# mini-v1_12-macrofab.net
KiCad netlist of a schematic drawn in EAGLE
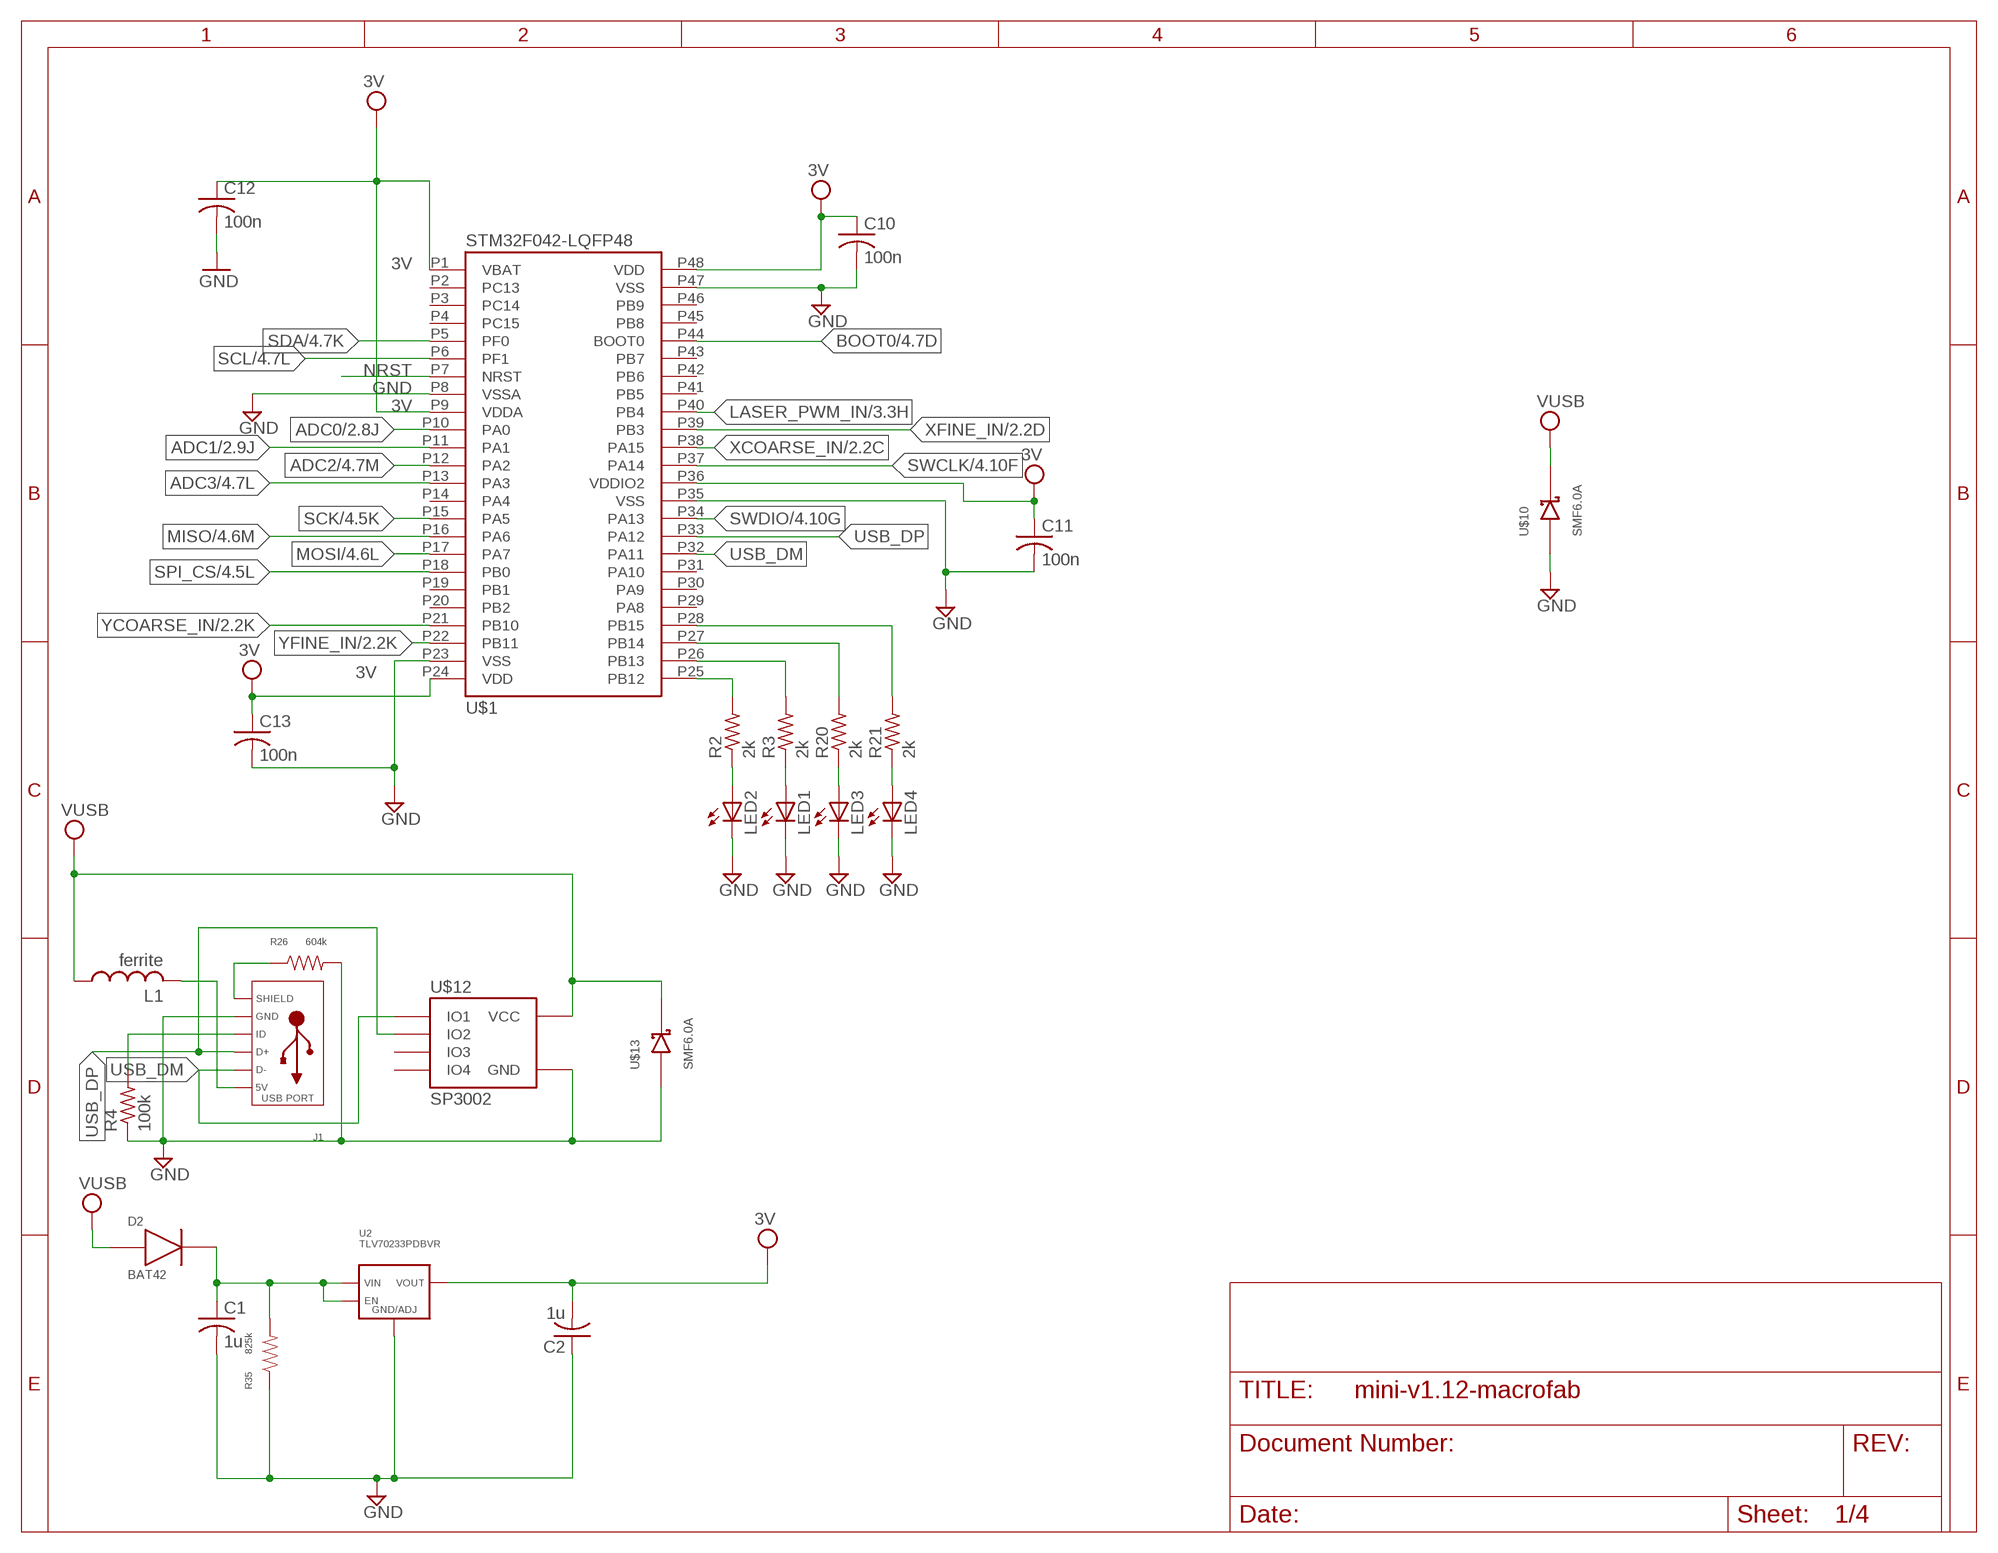
[diagram p0: schematic, sheet 1]
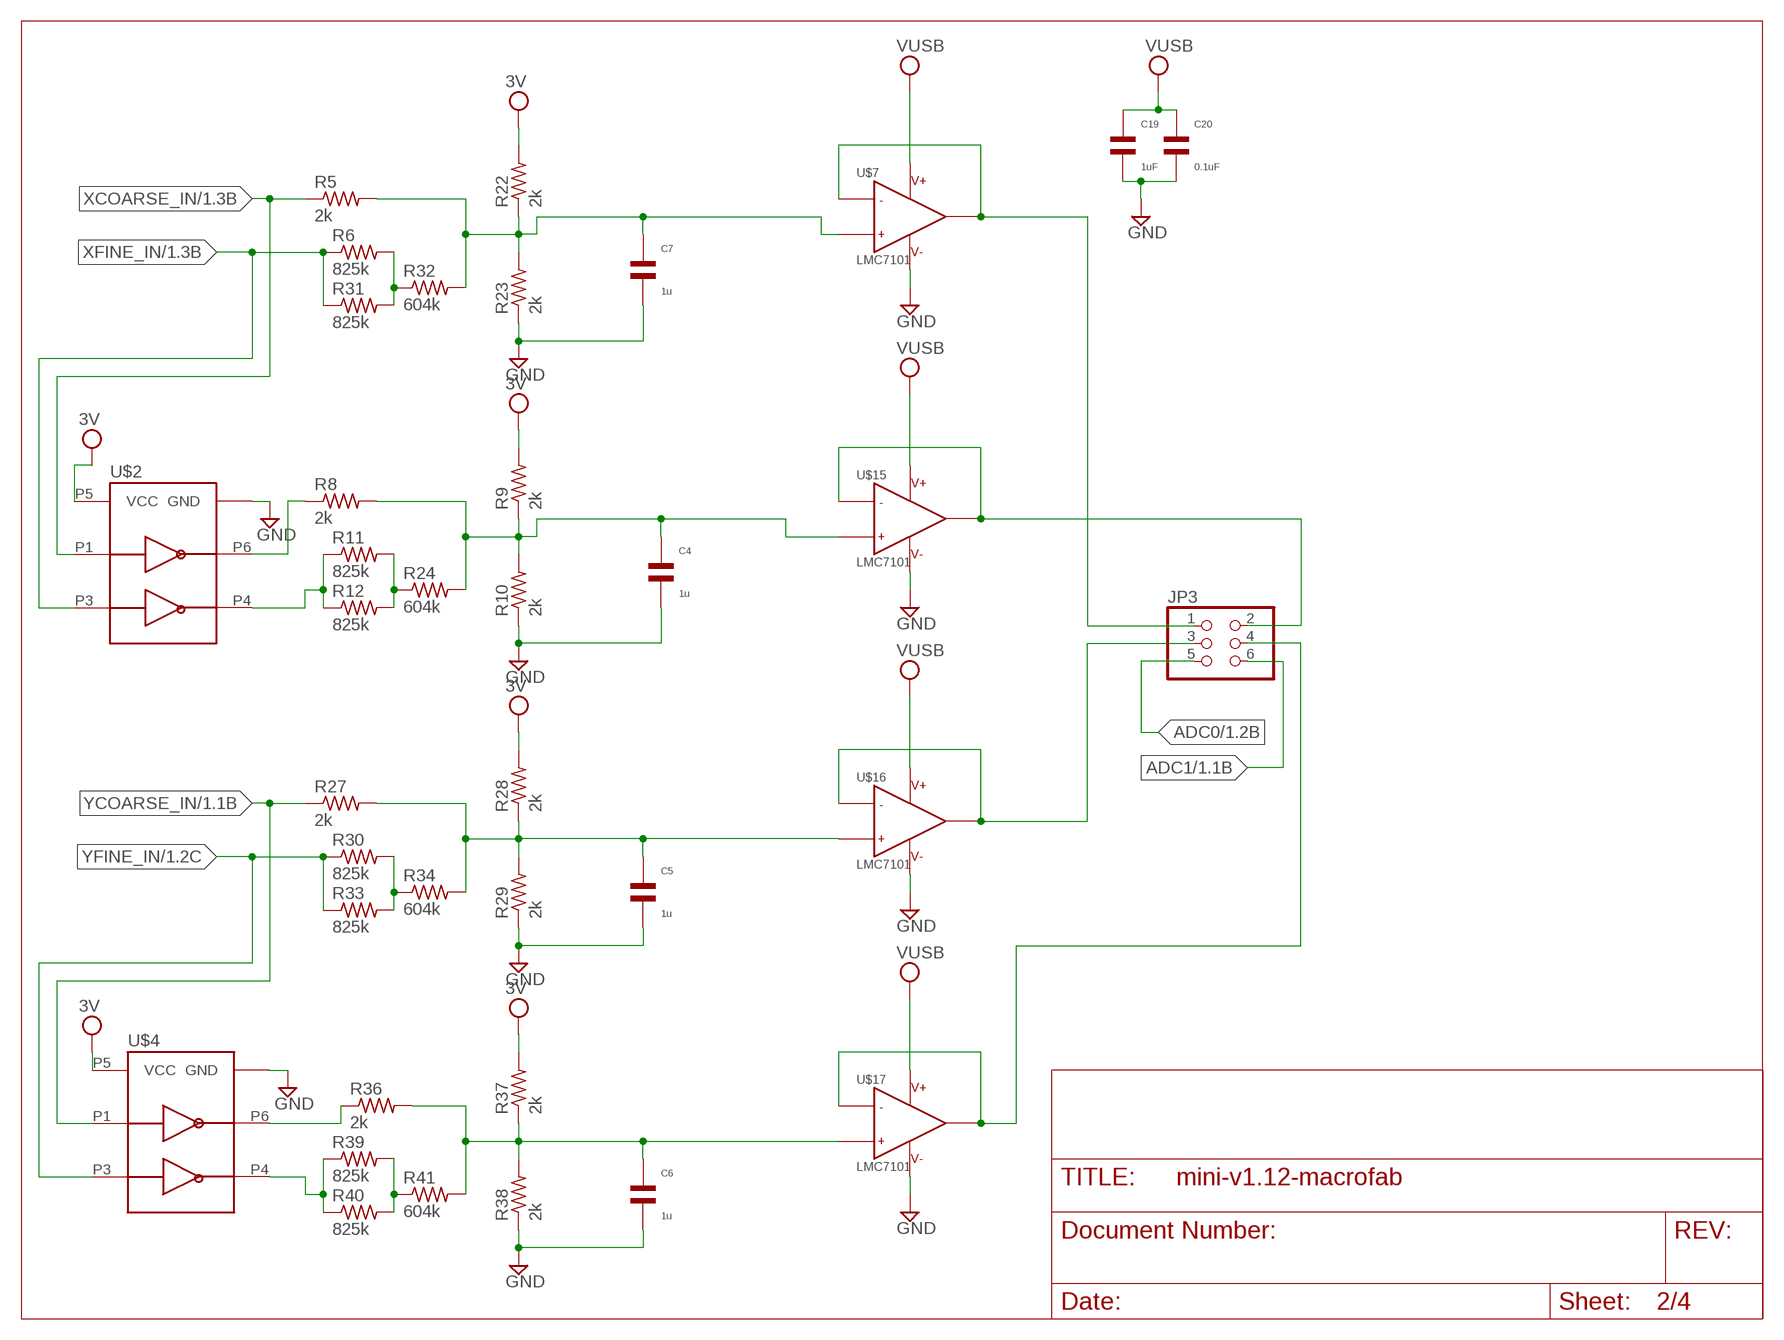
[diagram p1: schematic, sheet 2]
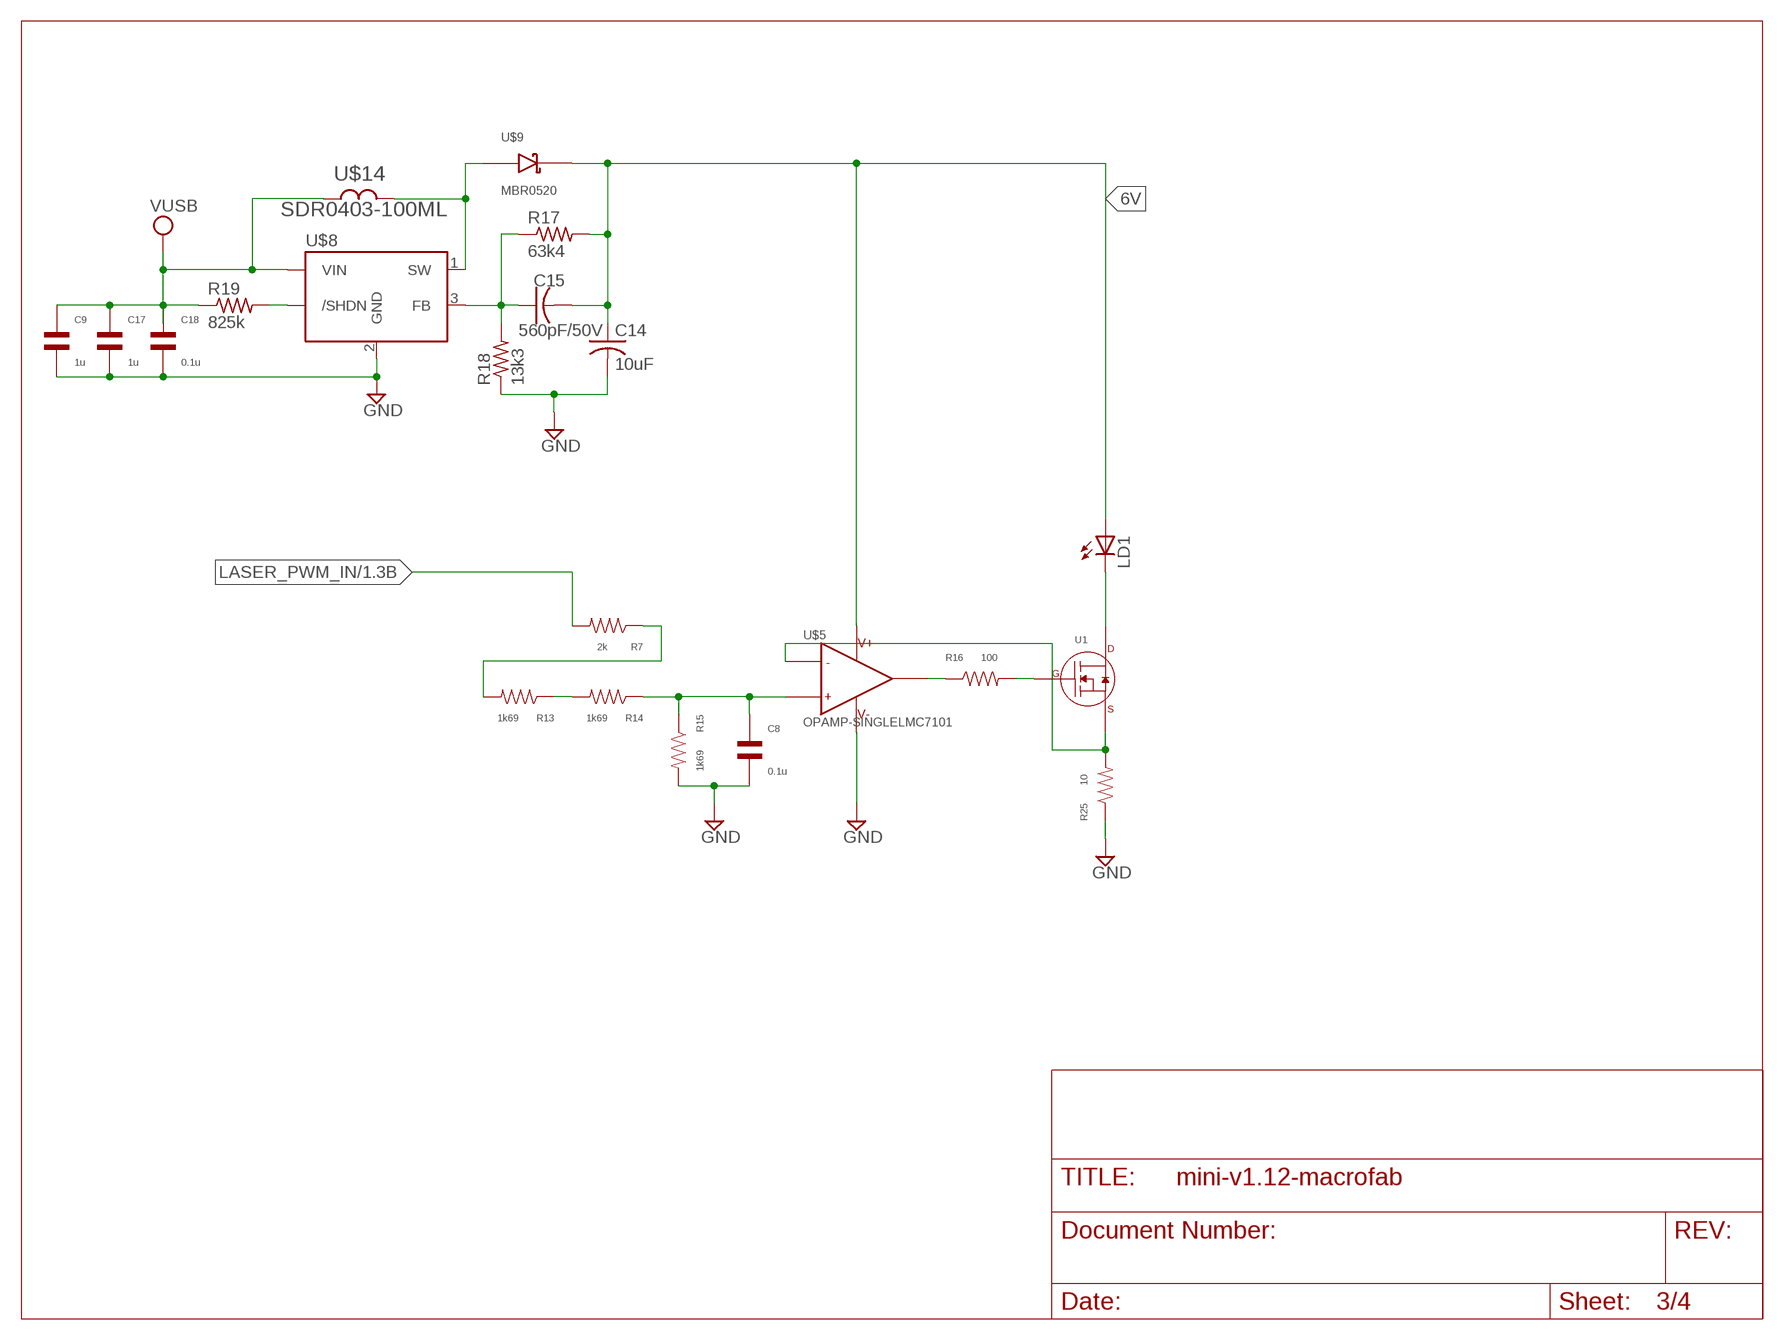
[diagram p2: schematic, sheet 3]
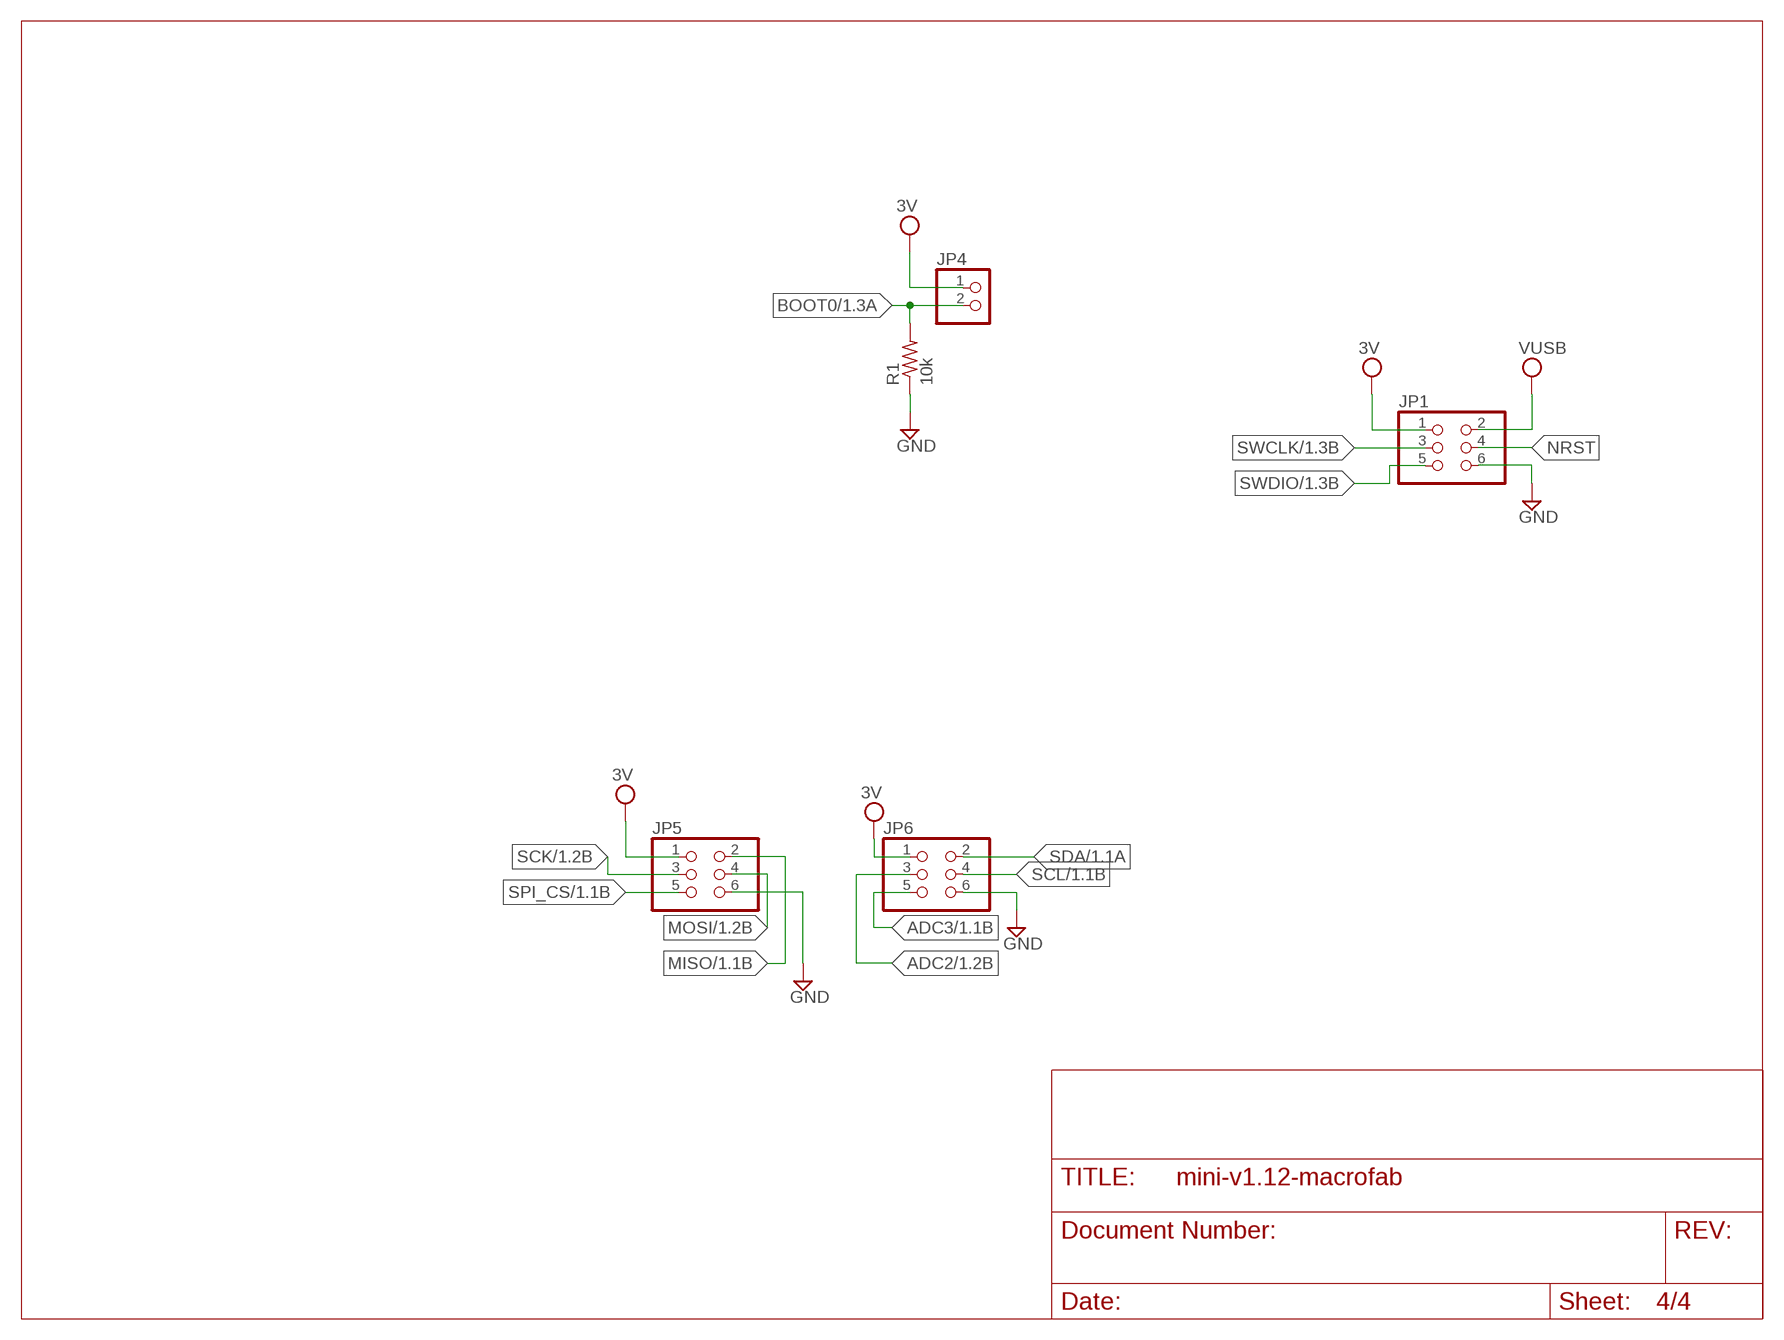
[diagram p3: schematic, sheet 4]

(export (version "E")
  (design (tool "Eeschema 10.0.6"))
  (components
    (comp (ref "C8")
      (value "0.1u")
      (footprint "eagle-import:C0603")
      (libsource (lib "eagle-import") (part "CAPACITOR_NP_0603"))
    )
    (comp (ref "C9")
      (value "1u")
      (footprint "eagle-import:C0603")
      (libsource (lib "eagle-import") (part "CAPACITOR_NP_0603"))
    )
    (comp (ref "C14")
      (value "10uF")
      (footprint "eagle-import:C0603")
      (libsource (lib "eagle-import") (part "C-USC0603"))
    )
    (comp (ref "C15")
      (value "560pF/50V")
      (footprint "eagle-import:C0603")
      (libsource (lib "eagle-import") (part "C-USC0603"))
    )
    (comp (ref "C17")
      (value "1u")
      (footprint "eagle-import:C0603")
      (libsource (lib "eagle-import") (part "CAPACITOR_NP_0603"))
    )
    (comp (ref "C18")
      (value "0.1u")
      (footprint "eagle-import:C0603")
      (libsource (lib "eagle-import") (part "CAPACITOR_NP_0603"))
    )
    (comp (ref "LD1")
      (value "LASERDIODELD2")
      (footprint "eagle-import:LASERDIODE2")
      (fields (field (name "MPN") "3 x (0552-2-15-15-11-27-10-0)"))
      (libsource (lib "eagle-import") (part "LASERDIODELD2"))
    )
    (comp (ref "R7")
      (value "2k")
      (footprint "eagle-import:R0603")
      (libsource (lib "eagle-import") (part "RESISTOR_0603"))
    )
    (comp (ref "R13")
      (value "1k69")
      (footprint "eagle-import:R0603")
      (libsource (lib "eagle-import") (part "RESISTOR_0603"))
    )
    (comp (ref "R14")
      (value "1k69")
      (footprint "eagle-import:R0603")
      (libsource (lib "eagle-import") (part "RESISTOR_0603"))
    )
    (comp (ref "R15")
      (value "1k69")
      (footprint "eagle-import:R0603")
      (libsource (lib "eagle-import") (part "RESISTOR_0603"))
    )
    (comp (ref "R16")
      (value "100")
      (footprint "eagle-import:R0603")
      (libsource (lib "eagle-import") (part "RESISTOR_0603"))
    )
    (comp (ref "R17")
      (value "63k4")
      (footprint "eagle-import:R0603")
      (libsource (lib "eagle-import") (part "R-US_R0603"))
    )
    (comp (ref "R18")
      (value "13k3")
      (footprint "eagle-import:R0603")
      (libsource (lib "eagle-import") (part "R-US_R0603"))
    )
    (comp (ref "R19")
      (value "825k")
      (footprint "eagle-import:R0603")
      (libsource (lib "eagle-import") (part "R-US_R0603"))
    )
    (comp (ref "R25")
      (value "10")
      (footprint "eagle-import:R0603")
      (libsource (lib "eagle-import") (part "RESISTOR_0603"))
    )
    (comp (ref "U$5")
      (value "OPAMP-SINGLELMC7101")
      (footprint "eagle-import:SOT23-5")
      (libsource (lib "eagle-import") (part "OPAMP-SINGLELMC7101"))
    )
    (comp (ref "U$8")
      (value "LMR62014")
      (footprint "eagle-import:SOT23-5")
      (libsource (lib "eagle-import") (part "LMR62014"))
    )
    (comp (ref "U$9")
      (value "MBR0520")
      (footprint "eagle-import:SOD123")
      (libsource (lib "eagle-import") (part "MBR0520"))
    )
    (comp (ref "U$14")
      (value "SDR0403-100ML")
      (footprint "eagle-import:SDR0403")
      (libsource (lib "eagle-import") (part "SDR0403"))
    )
    (comp (ref "U1")
      (value "N-CHANNEL_FET_SOT-23-3")
      (footprint "eagle-import:SOT-23-3")
      (libsource (lib "eagle-import") (part "N-CHANNEL_FET_SOT-23-3"))
    )
    (comp (ref "C1")
      (value "1u")
      (footprint "eagle-import:C0603")
      (libsource (lib "eagle-import") (part "C-USC0603"))
    )
    (comp (ref "C2")
      (value "1u")
      (footprint "eagle-import:C0603")
      (libsource (lib "eagle-import") (part "C-USC0603"))
    )
    (comp (ref "C10")
      (value "100n")
      (footprint "eagle-import:C0603")
      (libsource (lib "eagle-import") (part "C-USC0603"))
    )
    (comp (ref "C11")
      (value "100n")
      (footprint "eagle-import:C0603")
      (libsource (lib "eagle-import") (part "C-USC0603"))
    )
    (comp (ref "C12")
      (value "100n")
      (footprint "eagle-import:C0603")
      (libsource (lib "eagle-import") (part "C-USC0603"))
    )
    (comp (ref "C13")
      (value "100n")
      (footprint "eagle-import:C0603")
      (libsource (lib "eagle-import") (part "C-USC0603"))
    )
    (comp (ref "D2")
      (value "BAT42")
      (footprint "eagle-import:SOD323")
      (libsource (lib "eagle-import") (part "BAT60A"))
    )
    (comp (ref "J1")
      (value "USB_MICRO_RIGHT")
      (footprint "eagle-import:MICROUSB-RIGHT")
      (libsource (lib "eagle-import") (part "USB_MICRO_RIGHT"))
    )
    (comp (ref "L1")
      (value "ferrite")
      (footprint "eagle-import:C0603")
      (libsource (lib "eagle-import") (part "L-US"))
    )
    (comp (ref "LED1")
      (value "LEDCHIP-LED0603")
      (footprint "eagle-import:CHIP-LED0603")
      (libsource (lib "eagle-import") (part "LEDCHIP-LED0603"))
    )
    (comp (ref "LED2")
      (value "LEDCHIP-LED0603")
      (footprint "eagle-import:CHIP-LED0603")
      (libsource (lib "eagle-import") (part "LEDCHIP-LED0603"))
    )
    (comp (ref "LED3")
      (value "LEDCHIP-LED0603")
      (footprint "eagle-import:CHIP-LED0603")
      (libsource (lib "eagle-import") (part "LEDCHIP-LED0603"))
    )
    (comp (ref "LED4")
      (value "LEDCHIP-LED0603")
      (footprint "eagle-import:CHIP-LED0603")
      (libsource (lib "eagle-import") (part "LEDCHIP-LED0603"))
    )
    (comp (ref "R2")
      (value "2k")
      (footprint "eagle-import:R0603")
      (libsource (lib "eagle-import") (part "R-US_R0603"))
    )
    (comp (ref "R3")
      (value "2k")
      (footprint "eagle-import:R0603")
      (libsource (lib "eagle-import") (part "R-US_R0603"))
    )
    (comp (ref "R4")
      (value "100k")
      (footprint "eagle-import:R0603")
      (libsource (lib "eagle-import") (part "R-US_R0603"))
    )
    (comp (ref "R20")
      (value "2k")
      (footprint "eagle-import:R0603")
      (libsource (lib "eagle-import") (part "R-US_R0603"))
    )
    (comp (ref "R21")
      (value "2k")
      (footprint "eagle-import:R0603")
      (libsource (lib "eagle-import") (part "R-US_R0603"))
    )
    (comp (ref "R26")
      (value "604k")
      (footprint "eagle-import:R0603")
      (libsource (lib "eagle-import") (part "RESISTOR_0603"))
    )
    (comp (ref "R35")
      (value "825k")
      (footprint "eagle-import:R0603")
      (libsource (lib "eagle-import") (part "RESISTOR_0603"))
    )
    (comp (ref "U$1")
      (value "STM32F042-LQFP48")
      (footprint "eagle-import:LQFP48")
      (libsource (lib "eagle-import") (part "STM32F042-LQFP48"))
    )
    (comp (ref "U$10")
      (value "SMF6.0A")
      (footprint "eagle-import:SOD123")
      (libsource (lib "eagle-import") (part "MBR0520"))
    )
    (comp (ref "U$12")
      (value "SP3002")
      (footprint "eagle-import:SC70-6")
      (libsource (lib "eagle-import") (part "SP3002"))
    )
    (comp (ref "U$13")
      (value "SMF6.0A")
      (footprint "eagle-import:SOD123")
      (libsource (lib "eagle-import") (part "MBR0520"))
    )
    (comp (ref "U2")
      (value "TLV70233PDBVR")
      (footprint "eagle-import:SOT-23-5")
      (libsource (lib "eagle-import") (part "TLV70233PDBVR"))
    )
    (comp (ref "C4")
      (value "1u")
      (footprint "eagle-import:C0603")
      (libsource (lib "eagle-import") (part "CAPACITOR_NP_0603"))
    )
    (comp (ref "C5")
      (value "1u")
      (footprint "eagle-import:C0603")
      (libsource (lib "eagle-import") (part "CAPACITOR_NP_0603"))
    )
    (comp (ref "C6")
      (value "1u")
      (footprint "eagle-import:C0603")
      (libsource (lib "eagle-import") (part "CAPACITOR_NP_0603"))
    )
    (comp (ref "C7")
      (value "1u")
      (footprint "eagle-import:C0603")
      (libsource (lib "eagle-import") (part "CAPACITOR_NP_0603"))
    )
    (comp (ref "C19")
      (value "1uF")
      (footprint "eagle-import:C0603")
      (libsource (lib "eagle-import") (part "CAPACITOR_NP_0603"))
    )
    (comp (ref "C20")
      (value "0.1uF")
      (footprint "eagle-import:C0603")
      (libsource (lib "eagle-import") (part "CAPACITOR_NP_0603"))
    )
    (comp (ref "JP3")
      (value "PINHD-2X3")
      (footprint "eagle-import:2X03")
      (libsource (lib "eagle-import") (part "PINHD-2X3"))
    )
    (comp (ref "R5")
      (value "2k")
      (footprint "eagle-import:R0603")
      (libsource (lib "eagle-import") (part "R-US_R0603"))
    )
    (comp (ref "R6")
      (value "825k")
      (footprint "eagle-import:R0603")
      (libsource (lib "eagle-import") (part "R-US_R0603"))
    )
    (comp (ref "R8")
      (value "2k")
      (footprint "eagle-import:R0603")
      (libsource (lib "eagle-import") (part "R-US_R0603"))
    )
    (comp (ref "R9")
      (value "2k")
      (footprint "eagle-import:R0603")
      (libsource (lib "eagle-import") (part "R-US_R0603"))
    )
    (comp (ref "R10")
      (value "2k")
      (footprint "eagle-import:R0603")
      (libsource (lib "eagle-import") (part "R-US_R0603"))
    )
    (comp (ref "R11")
      (value "825k")
      (footprint "eagle-import:R0603")
      (libsource (lib "eagle-import") (part "R-US_R0603"))
    )
    (comp (ref "R12")
      (value "825k")
      (footprint "eagle-import:R0603")
      (libsource (lib "eagle-import") (part "R-US_R0603"))
    )
    (comp (ref "R22")
      (value "2k")
      (footprint "eagle-import:R0603")
      (libsource (lib "eagle-import") (part "R-US_R0603"))
    )
    (comp (ref "R23")
      (value "2k")
      (footprint "eagle-import:R0603")
      (libsource (lib "eagle-import") (part "R-US_R0603"))
    )
    (comp (ref "R24")
      (value "604k")
      (footprint "eagle-import:R0603")
      (libsource (lib "eagle-import") (part "R-US_R0603"))
    )
    (comp (ref "R27")
      (value "2k")
      (footprint "eagle-import:R0603")
      (libsource (lib "eagle-import") (part "R-US_R0603"))
    )
    (comp (ref "R28")
      (value "2k")
      (footprint "eagle-import:R0603")
      (libsource (lib "eagle-import") (part "R-US_R0603"))
    )
    (comp (ref "R29")
      (value "2k")
      (footprint "eagle-import:R0603")
      (libsource (lib "eagle-import") (part "R-US_R0603"))
    )
    (comp (ref "R30")
      (value "825k")
      (footprint "eagle-import:R0603")
      (libsource (lib "eagle-import") (part "R-US_R0603"))
    )
    (comp (ref "R31")
      (value "825k")
      (footprint "eagle-import:R0603")
      (libsource (lib "eagle-import") (part "R-US_R0603"))
    )
    (comp (ref "R32")
      (value "604k")
      (footprint "eagle-import:R0603")
      (libsource (lib "eagle-import") (part "R-US_R0603"))
    )
    (comp (ref "R33")
      (value "825k")
      (footprint "eagle-import:R0603")
      (libsource (lib "eagle-import") (part "R-US_R0603"))
    )
    (comp (ref "R34")
      (value "604k")
      (footprint "eagle-import:R0603")
      (libsource (lib "eagle-import") (part "R-US_R0603"))
    )
    (comp (ref "R36")
      (value "2k")
      (footprint "eagle-import:R0603")
      (libsource (lib "eagle-import") (part "R-US_R0603"))
    )
    (comp (ref "R37")
      (value "2k")
      (footprint "eagle-import:R0603")
      (libsource (lib "eagle-import") (part "R-US_R0603"))
    )
    (comp (ref "R38")
      (value "2k")
      (footprint "eagle-import:R0603")
      (libsource (lib "eagle-import") (part "R-US_R0603"))
    )
    (comp (ref "R39")
      (value "825k")
      (footprint "eagle-import:R0603")
      (libsource (lib "eagle-import") (part "R-US_R0603"))
    )
    (comp (ref "R40")
      (value "825k")
      (footprint "eagle-import:R0603")
      (libsource (lib "eagle-import") (part "R-US_R0603"))
    )
    (comp (ref "R41")
      (value "604k")
      (footprint "eagle-import:R0603")
      (libsource (lib "eagle-import") (part "R-US_R0603"))
    )
    (comp (ref "U$2")
      (value "NC7WZ14P6X")
      (footprint "eagle-import:SC70-6")
      (libsource (lib "eagle-import") (part "NC7WZ14P6X"))
    )
    (comp (ref "U$4")
      (value "NC7WZ14P6X")
      (footprint "eagle-import:SC70-6")
      (libsource (lib "eagle-import") (part "NC7WZ14P6X"))
    )
    (comp (ref "U$7")
      (value "LMC7101")
      (footprint "eagle-import:SOT23-5")
      (libsource (lib "eagle-import") (part "LMC7101"))
    )
    (comp (ref "U$15")
      (value "LMC7101")
      (footprint "eagle-import:SOT23-5")
      (libsource (lib "eagle-import") (part "LMC7101"))
    )
    (comp (ref "U$16")
      (value "LMC7101")
      (footprint "eagle-import:SOT23-5")
      (libsource (lib "eagle-import") (part "LMC7101"))
    )
    (comp (ref "U$17")
      (value "LMC7101")
      (footprint "eagle-import:SOT23-5")
      (libsource (lib "eagle-import") (part "LMC7101"))
    )
    (comp (ref "JP1")
      (value "PINHD-2X3")
      (footprint "eagle-import:2X03")
      (libsource (lib "eagle-import") (part "PINHD-2X3"))
    )
    (comp (ref "JP4")
      (value "PINHD-1X2")
      (footprint "eagle-import:1X02")
      (libsource (lib "eagle-import") (part "PINHD-1X2"))
    )
    (comp (ref "JP5")
      (value "PINHD-2X3")
      (footprint "eagle-import:2X03")
      (libsource (lib "eagle-import") (part "PINHD-2X3"))
    )
    (comp (ref "JP6")
      (value "PINHD-2X3")
      (footprint "eagle-import:2X03")
      (libsource (lib "eagle-import") (part "PINHD-2X3"))
    )
    (comp (ref "R1")
      (value "10k")
      (footprint "eagle-import:R0603")
      (libsource (lib "eagle-import") (part "R-US_R0603"))
    )
  )
  (nets
    (net (code "1") (name "3V") (class "Default")
      (node (ref "C10") (pin "1") (pinfunction "1_1") (pintype "passive"))
      (node (ref "C11") (pin "1") (pinfunction "1_1") (pintype "passive"))
      (node (ref "C12") (pin "1") (pinfunction "1_1") (pintype "passive"))
      (node (ref "C13") (pin "1") (pinfunction "1_1") (pintype "passive"))
      (node (ref "C2") (pin "2") (pinfunction "2_2") (pintype "passive"))
      (node (ref "JP1") (pin "1") (pinfunction "1_1") (pintype "passive"))
      (node (ref "JP4") (pin "1") (pinfunction "1_1") (pintype "passive"))
      (node (ref "JP5") (pin "1") (pinfunction "1_1") (pintype "passive"))
      (node (ref "JP6") (pin "1") (pinfunction "1_1") (pintype "passive"))
      (node (ref "R22") (pin "2") (pinfunction "2_2") (pintype "passive"))
      (node (ref "R28") (pin "2") (pinfunction "2_2") (pintype "passive"))
      (node (ref "R37") (pin "2") (pinfunction "2_2") (pintype "passive"))
      (node (ref "R9") (pin "2") (pinfunction "2_2") (pintype "passive"))
      (node (ref "U$1") (pin "P1") (pinfunction "VBAT_P1") (pintype "bidirectional"))
      (node (ref "U$1") (pin "P24") (pinfunction "VDD_P24") (pintype "bidirectional"))
      (node (ref "U$1") (pin "P36") (pinfunction "VDDIO2_P36") (pintype "bidirectional"))
      (node (ref "U$1") (pin "P48") (pinfunction "VDD_P48") (pintype "bidirectional"))
      (node (ref "U$1") (pin "P9") (pinfunction "VDDA_P9") (pintype "bidirectional"))
      (node (ref "U$2") (pin "P5") (pinfunction "VCC_P5") (pintype "power_in"))
      (node (ref "U$4") (pin "P5") (pinfunction "VCC_P5") (pintype "power_in"))
      (node (ref "U2") (pin "P$5") (pinfunction "VOUT_P$5") (pintype "bidirectional"))
    )
    (net (code "2") (name "6V") (class "Default")
      (node (ref "C14") (pin "1") (pinfunction "1_1") (pintype "passive"))
      (node (ref "C15") (pin "2") (pinfunction "2_2") (pintype "passive"))
      (node (ref "LD1") (pin "P$1") (pinfunction "A_P$1") (pintype "passive"))
      (node (ref "R17") (pin "2") (pinfunction "2_2") (pintype "passive"))
      (node (ref "U$5") (pin "2") (pinfunction "V+_2") (pintype "power_in"))
      (node (ref "U$9") (pin "CATHODE") (pinfunction "CATHODE_CATHODE") (pintype "bidirectional"))
    )
    (net (code "3") (name "ADC0") (class "Default")
      (node (ref "JP3") (pin "5") (pinfunction "5_5") (pintype "passive"))
      (node (ref "U$1") (pin "P10") (pinfunction "PA0_P10") (pintype "bidirectional"))
    )
    (net (code "4") (name "ADC1") (class "Default")
      (node (ref "JP3") (pin "6") (pinfunction "6_6") (pintype "passive"))
      (node (ref "U$1") (pin "P11") (pinfunction "PA1_P11") (pintype "bidirectional"))
    )
    (net (code "5") (name "ADC2") (class "Default")
      (node (ref "JP6") (pin "3") (pinfunction "3_3") (pintype "passive"))
      (node (ref "U$1") (pin "P12") (pinfunction "PA2_P12") (pintype "bidirectional"))
    )
    (net (code "6") (name "ADC3") (class "Default")
      (node (ref "JP6") (pin "5") (pinfunction "5_5") (pintype "passive"))
      (node (ref "U$1") (pin "P13") (pinfunction "PA3_P13") (pintype "bidirectional"))
    )
    (net (code "7") (name "BOOT0") (class "Default")
      (node (ref "JP4") (pin "2") (pinfunction "2_2") (pintype "passive"))
      (node (ref "R1") (pin "2") (pinfunction "2_2") (pintype "passive"))
      (node (ref "U$1") (pin "P44") (pinfunction "BOOT0_P44") (pintype "bidirectional"))
    )
    (net (code "8") (name "GND") (class "Default")
      (node (ref "C1") (pin "2") (pinfunction "2_2") (pintype "passive"))
      (node (ref "C10") (pin "2") (pinfunction "2_2") (pintype "passive"))
      (node (ref "C11") (pin "2") (pinfunction "2_2") (pintype "passive"))
      (node (ref "C12") (pin "2") (pinfunction "2_2") (pintype "passive"))
      (node (ref "C13") (pin "2") (pinfunction "2_2") (pintype "passive"))
      (node (ref "C14") (pin "2") (pinfunction "2_2") (pintype "passive"))
      (node (ref "C17") (pin "P$2") (pinfunction "P$2_P$2") (pintype "passive"))
      (node (ref "C18") (pin "P$2") (pinfunction "P$2_P$2") (pintype "passive"))
      (node (ref "C19") (pin "P$2") (pinfunction "P$2_P$2") (pintype "passive"))
      (node (ref "C2") (pin "1") (pinfunction "1_1") (pintype "passive"))
      (node (ref "C20") (pin "P$2") (pinfunction "P$2_P$2") (pintype "passive"))
      (node (ref "C4") (pin "P$2") (pinfunction "P$2_P$2") (pintype "passive"))
      (node (ref "C5") (pin "P$2") (pinfunction "P$2_P$2") (pintype "passive"))
      (node (ref "C6") (pin "P$2") (pinfunction "P$2_P$2") (pintype "passive"))
      (node (ref "C7") (pin "P$2") (pinfunction "P$2_P$2") (pintype "passive"))
      (node (ref "C8") (pin "P$2") (pinfunction "P$2_P$2") (pintype "passive"))
      (node (ref "C9") (pin "P$2") (pinfunction "P$2_P$2") (pintype "passive"))
      (node (ref "J1") (pin "5") (pinfunction "GND_5") (pintype "power_in"))
      (node (ref "JP1") (pin "6") (pinfunction "6_6") (pintype "passive"))
      (node (ref "JP5") (pin "6") (pinfunction "6_6") (pintype "passive"))
      (node (ref "JP6") (pin "6") (pinfunction "6_6") (pintype "passive"))
      (node (ref "LED1") (pin "C") (pinfunction "C_C") (pintype "passive"))
      (node (ref "LED2") (pin "C") (pinfunction "C_C") (pintype "passive"))
      (node (ref "LED3") (pin "C") (pinfunction "C_C") (pintype "passive"))
      (node (ref "LED4") (pin "C") (pinfunction "C_C") (pintype "passive"))
      (node (ref "R1") (pin "1") (pinfunction "1_1") (pintype "passive"))
      (node (ref "R10") (pin "1") (pinfunction "1_1") (pintype "passive"))
      (node (ref "R15") (pin "P$2") (pinfunction "P$2_P$2") (pintype "passive"))
      (node (ref "R18") (pin "1") (pinfunction "1_1") (pintype "passive"))
      (node (ref "R23") (pin "1") (pinfunction "1_1") (pintype "passive"))
      (node (ref "R25") (pin "P$1") (pinfunction "P$1_P$1") (pintype "passive"))
      (node (ref "R26") (pin "P$2") (pinfunction "P$2_P$2") (pintype "passive"))
      (node (ref "R29") (pin "1") (pinfunction "1_1") (pintype "passive"))
      (node (ref "R35") (pin "P$1") (pinfunction "P$1_P$1") (pintype "passive"))
      (node (ref "R38") (pin "1") (pinfunction "1_1") (pintype "passive"))
      (node (ref "R4") (pin "1") (pinfunction "1_1") (pintype "passive"))
      (node (ref "U$1") (pin "P23") (pinfunction "VSS_P23") (pintype "bidirectional"))
      (node (ref "U$1") (pin "P35") (pinfunction "VSS_P35") (pintype "bidirectional"))
      (node (ref "U$1") (pin "P47") (pinfunction "VSS_P47") (pintype "bidirectional"))
      (node (ref "U$1") (pin "P8") (pinfunction "VSSA_P8") (pintype "bidirectional"))
      (node (ref "U$10") (pin "ANODE") (pinfunction "ANODE_ANODE") (pintype "bidirectional"))
      (node (ref "U$12") (pin "P2") (pinfunction "GND_P2") (pintype "power_in"))
      (node (ref "U$13") (pin "ANODE") (pinfunction "ANODE_ANODE") (pintype "bidirectional"))
      (node (ref "U$15") (pin "5") (pinfunction "P5_5") (pintype "power_in"))
      (node (ref "U$16") (pin "5") (pinfunction "P5_5") (pintype "power_in"))
      (node (ref "U$17") (pin "5") (pinfunction "P5_5") (pintype "power_in"))
      (node (ref "U$2") (pin "P2") (pinfunction "GND_P2") (pintype "power_in"))
      (node (ref "U$4") (pin "P2") (pinfunction "GND_P2") (pintype "power_in"))
      (node (ref "U$5") (pin "5") (pinfunction "V-_5") (pintype "power_in"))
      (node (ref "U$7") (pin "5") (pinfunction "P5_5") (pintype "power_in"))
      (node (ref "U$8") (pin "2") (pinfunction "GND_2") (pintype "bidirectional"))
      (node (ref "U2") (pin "P$2") (pinfunction "GND/ADJ_P$2") (pintype "bidirectional"))
    )
    (net (code "9") (name "LASER_PWM_IN") (class "Default")
      (node (ref "R7") (pin "P$2") (pinfunction "P$2_P$2") (pintype "passive"))
      (node (ref "U$1") (pin "P40") (pinfunction "PB4_P40") (pintype "bidirectional"))
    )
    (net (code "10") (name "MISO") (class "Default")
      (node (ref "JP5") (pin "2") (pinfunction "2_2") (pintype "passive"))
      (node (ref "U$1") (pin "P16") (pinfunction "PA6_P16") (pintype "bidirectional"))
    )
    (net (code "11") (name "MOSI") (class "Default")
      (node (ref "JP5") (pin "4") (pinfunction "4_4") (pintype "passive"))
      (node (ref "U$1") (pin "P17") (pinfunction "PA7_P17") (pintype "bidirectional"))
    )
    (net (code "12") (name "NRST") (class "Default")
      (node (ref "JP1") (pin "4") (pinfunction "4_4") (pintype "passive"))
      (node (ref "U$1") (pin "P7") (pinfunction "NRST_P7") (pintype "bidirectional"))
    )
    (net (code "13") (name "Net-(J1-5V)") (class "Default")
      (node (ref "J1") (pin "1") (pinfunction "5V_1") (pintype "power_in"))
      (node (ref "L1") (pin "2") (pinfunction "2_2") (pintype "passive"))
    )
    (net (code "14") (name "Net-(J1-ID)") (class "Default")
      (node (ref "J1") (pin "4") (pinfunction "ID_4") (pintype "bidirectional"))
      (node (ref "R4") (pin "2") (pinfunction "2_2") (pintype "passive"))
    )
    (net (code "15") (name "Net-(J1-SLD-PadS1)") (class "Default")
      (node (ref "J1") (pin "S1") (pinfunction "SLD_S1") (pintype "power_in"))
      (node (ref "J1") (pin "S2") (pinfunction "SLD_S2") (pintype "power_in"))
      (node (ref "J1") (pin "S3") (pinfunction "SLD_S3") (pintype "power_in"))
      (node (ref "J1") (pin "S4") (pinfunction "SLD_S4") (pintype "power_in"))
      (node (ref "J1") (pin "S5") (pinfunction "SLD_S5") (pintype "power_in"))
      (node (ref "J1") (pin "S6") (pinfunction "SLD_S6") (pintype "power_in"))
      (node (ref "R26") (pin "P$1") (pinfunction "P$1_P$1") (pintype "passive"))
    )
    (net (code "16") (name "Net-(LD1-C)") (class "Default")
      (node (ref "LD1") (pin "P$3") (pinfunction "C_P$3") (pintype "passive"))
      (node (ref "U1") (pin "P$3") (pinfunction "DRAIN_P$3") (pintype "bidirectional"))
    )
    (net (code "17") (name "Net-(LED1-PadA)") (class "Default")
      (node (ref "LED1") (pin "A") (pinfunction "A_A") (pintype "passive"))
      (node (ref "R3") (pin "1") (pinfunction "1_1") (pintype "passive"))
    )
    (net (code "18") (name "Net-(LED2-PadA)") (class "Default")
      (node (ref "LED2") (pin "A") (pinfunction "A_A") (pintype "passive"))
      (node (ref "R2") (pin "1") (pinfunction "1_1") (pintype "passive"))
    )
    (net (code "19") (name "Net-(LED3-PadA)") (class "Default")
      (node (ref "LED3") (pin "A") (pinfunction "A_A") (pintype "passive"))
      (node (ref "R20") (pin "1") (pinfunction "1_1") (pintype "passive"))
    )
    (net (code "20") (name "Net-(LED4-PadA)") (class "Default")
      (node (ref "LED4") (pin "A") (pinfunction "A_A") (pintype "passive"))
      (node (ref "R21") (pin "1") (pinfunction "1_1") (pintype "passive"))
    )
    (net (code "21") (name "Net-(R11-Pad2)") (class "Default")
      (node (ref "R11") (pin "2") (pinfunction "2_2") (pintype "passive"))
      (node (ref "R12") (pin "2") (pinfunction "2_2") (pintype "passive"))
      (node (ref "R24") (pin "1") (pinfunction "1_1") (pintype "passive"))
    )
    (net (code "22") (name "Net-(R13-PadP$1)") (class "Default")
      (node (ref "R13") (pin "P$1") (pinfunction "P$1_P$1") (pintype "passive"))
      (node (ref "R14") (pin "P$2") (pinfunction "P$2_P$2") (pintype "passive"))
    )
    (net (code "23") (name "Net-(R13-PadP$2)") (class "Default")
      (node (ref "R13") (pin "P$2") (pinfunction "P$2_P$2") (pintype "passive"))
      (node (ref "R7") (pin "P$1") (pinfunction "P$1_P$1") (pintype "passive"))
    )
    (net (code "24") (name "Net-(R30-Pad2)") (class "Default")
      (node (ref "R30") (pin "2") (pinfunction "2_2") (pintype "passive"))
      (node (ref "R33") (pin "2") (pinfunction "2_2") (pintype "passive"))
      (node (ref "R34") (pin "1") (pinfunction "1_1") (pintype "passive"))
    )
    (net (code "25") (name "Net-(R31-Pad2)") (class "Default")
      (node (ref "R31") (pin "2") (pinfunction "2_2") (pintype "passive"))
      (node (ref "R32") (pin "1") (pinfunction "1_1") (pintype "passive"))
      (node (ref "R6") (pin "2") (pinfunction "2_2") (pintype "passive"))
    )
    (net (code "26") (name "Net-(R39-Pad2)") (class "Default")
      (node (ref "R39") (pin "2") (pinfunction "2_2") (pintype "passive"))
      (node (ref "R40") (pin "2") (pinfunction "2_2") (pintype "passive"))
      (node (ref "R41") (pin "1") (pinfunction "1_1") (pintype "passive"))
    )
    (net (code "27") (name "Net-(U$1-PB12)") (class "Default")
      (node (ref "R2") (pin "2") (pinfunction "2_2") (pintype "passive"))
      (node (ref "U$1") (pin "P25") (pinfunction "PB12_P25") (pintype "bidirectional"))
    )
    (net (code "28") (name "Net-(U$1-PB13)") (class "Default")
      (node (ref "R3") (pin "2") (pinfunction "2_2") (pintype "passive"))
      (node (ref "U$1") (pin "P26") (pinfunction "PB13_P26") (pintype "bidirectional"))
    )
    (net (code "29") (name "Net-(U$1-PB14)") (class "Default")
      (node (ref "R20") (pin "2") (pinfunction "2_2") (pintype "passive"))
      (node (ref "U$1") (pin "P27") (pinfunction "PB14_P27") (pintype "bidirectional"))
    )
    (net (code "30") (name "Net-(U$1-PB15)") (class "Default")
      (node (ref "R21") (pin "2") (pinfunction "2_2") (pintype "passive"))
      (node (ref "U$1") (pin "P28") (pinfunction "PB15_P28") (pintype "bidirectional"))
    )
    (net (code "31") (name "Net-(U$2-Y1)") (class "Default")
      (node (ref "R8") (pin "1") (pinfunction "1_1") (pintype "passive"))
      (node (ref "U$2") (pin "P6") (pinfunction "Y1_P6") (pintype "output"))
    )
    (net (code "32") (name "Net-(U$2-Y2)") (class "Default")
      (node (ref "R11") (pin "1") (pinfunction "1_1") (pintype "passive"))
      (node (ref "R12") (pin "1") (pinfunction "1_1") (pintype "passive"))
      (node (ref "U$2") (pin "P4") (pinfunction "Y2_P4") (pintype "output"))
    )
    (net (code "33") (name "Net-(U$4-Y1)") (class "Default")
      (node (ref "R36") (pin "1") (pinfunction "1_1") (pintype "passive"))
      (node (ref "U$4") (pin "P6") (pinfunction "Y1_P6") (pintype "output"))
    )
    (net (code "34") (name "Net-(U$4-Y2)") (class "Default")
      (node (ref "R39") (pin "1") (pinfunction "1_1") (pintype "passive"))
      (node (ref "R40") (pin "1") (pinfunction "1_1") (pintype "passive"))
      (node (ref "U$4") (pin "P4") (pinfunction "Y2_P4") (pintype "output"))
    )
    (net (code "35") (name "Net-(U$5-IN+)") (class "Default")
      (node (ref "C8") (pin "P$1") (pinfunction "P$1_P$1") (pintype "passive"))
      (node (ref "R14") (pin "P$1") (pinfunction "P$1_P$1") (pintype "passive"))
      (node (ref "R15") (pin "P$1") (pinfunction "P$1_P$1") (pintype "passive"))
      (node (ref "U$5") (pin "3") (pinfunction "IN+_3") (pintype "bidirectional"))
    )
    (net (code "36") (name "Net-(U$5-IN-)") (class "Default")
      (node (ref "R25") (pin "P$2") (pinfunction "P$2_P$2") (pintype "passive"))
      (node (ref "U$5") (pin "4") (pinfunction "IN-_4") (pintype "bidirectional"))
      (node (ref "U1") (pin "P$2") (pinfunction "SOURCE_P$2") (pintype "bidirectional"))
    )
    (net (code "37") (name "Net-(U$5-OUT)") (class "Default")
      (node (ref "R16") (pin "P$1") (pinfunction "P$1_P$1") (pintype "passive"))
      (node (ref "U$5") (pin "1") (pinfunction "OUT_1") (pintype "bidirectional"))
    )
    (net (code "38") (name "Net-(U$7-P1)") (class "Default")
      (node (ref "JP3") (pin "1") (pinfunction "1_1") (pintype "passive"))
      (node (ref "U$7") (pin "1") (pinfunction "P1_1") (pintype "bidirectional"))
      (node (ref "U$7") (pin "4") (pinfunction "P4_4") (pintype "bidirectional"))
    )
    (net (code "39") (name "Net-(U$7-P3)") (class "Default")
      (node (ref "C7") (pin "P$1") (pinfunction "P$1_P$1") (pintype "passive"))
      (node (ref "R22") (pin "1") (pinfunction "1_1") (pintype "passive"))
      (node (ref "R23") (pin "2") (pinfunction "2_2") (pintype "passive"))
      (node (ref "R32") (pin "2") (pinfunction "2_2") (pintype "passive"))
      (node (ref "R5") (pin "2") (pinfunction "2_2") (pintype "passive"))
      (node (ref "U$7") (pin "3") (pinfunction "P3_3") (pintype "bidirectional"))
    )
    (net (code "40") (name "Net-(U$8-FB)") (class "Default")
      (node (ref "C15") (pin "1") (pinfunction "1_1") (pintype "passive"))
      (node (ref "R17") (pin "1") (pinfunction "1_1") (pintype "passive"))
      (node (ref "R18") (pin "2") (pinfunction "2_2") (pintype "passive"))
      (node (ref "U$8") (pin "3") (pinfunction "FB_3") (pintype "bidirectional"))
    )
    (net (code "41") (name "Net-(U$8-SW)") (class "Default")
      (node (ref "U$14") (pin "P$2") (pinfunction "P$2_P$2") (pintype "bidirectional"))
      (node (ref "U$8") (pin "1") (pinfunction "SW_1") (pintype "bidirectional"))
      (node (ref "U$9") (pin "ANODE") (pinfunction "ANODE_ANODE") (pintype "bidirectional"))
    )
    (net (code "42") (name "Net-(U$8-{slash}SHDN)") (class "Default")
      (node (ref "R19") (pin "2") (pinfunction "2_2") (pintype "passive"))
      (node (ref "U$8") (pin "4") (pinfunction "/SHDN_4") (pintype "bidirectional"))
    )
    (net (code "43") (name "Net-(U$15-P1)") (class "Default")
      (node (ref "JP3") (pin "2") (pinfunction "2_2") (pintype "passive"))
      (node (ref "U$15") (pin "1") (pinfunction "P1_1") (pintype "bidirectional"))
      (node (ref "U$15") (pin "4") (pinfunction "P4_4") (pintype "bidirectional"))
    )
    (net (code "44") (name "Net-(U$15-P3)") (class "Default")
      (node (ref "C4") (pin "P$1") (pinfunction "P$1_P$1") (pintype "passive"))
      (node (ref "R10") (pin "2") (pinfunction "2_2") (pintype "passive"))
      (node (ref "R24") (pin "2") (pinfunction "2_2") (pintype "passive"))
      (node (ref "R8") (pin "2") (pinfunction "2_2") (pintype "passive"))
      (node (ref "R9") (pin "1") (pinfunction "1_1") (pintype "passive"))
      (node (ref "U$15") (pin "3") (pinfunction "P3_3") (pintype "bidirectional"))
    )
    (net (code "45") (name "Net-(U$16-P1)") (class "Default")
      (node (ref "JP3") (pin "3") (pinfunction "3_3") (pintype "passive"))
      (node (ref "U$16") (pin "1") (pinfunction "P1_1") (pintype "bidirectional"))
      (node (ref "U$16") (pin "4") (pinfunction "P4_4") (pintype "bidirectional"))
    )
    (net (code "46") (name "Net-(U$16-P3)") (class "Default")
      (node (ref "C5") (pin "P$1") (pinfunction "P$1_P$1") (pintype "passive"))
      (node (ref "R27") (pin "2") (pinfunction "2_2") (pintype "passive"))
      (node (ref "R28") (pin "1") (pinfunction "1_1") (pintype "passive"))
      (node (ref "R29") (pin "2") (pinfunction "2_2") (pintype "passive"))
      (node (ref "R34") (pin "2") (pinfunction "2_2") (pintype "passive"))
      (node (ref "U$16") (pin "3") (pinfunction "P3_3") (pintype "bidirectional"))
    )
    (net (code "47") (name "Net-(U$17-P1)") (class "Default")
      (node (ref "JP3") (pin "4") (pinfunction "4_4") (pintype "passive"))
      (node (ref "U$17") (pin "1") (pinfunction "P1_1") (pintype "bidirectional"))
      (node (ref "U$17") (pin "4") (pinfunction "P4_4") (pintype "bidirectional"))
    )
    (net (code "48") (name "Net-(U$17-P3)") (class "Default")
      (node (ref "C6") (pin "P$1") (pinfunction "P$1_P$1") (pintype "passive"))
      (node (ref "R36") (pin "2") (pinfunction "2_2") (pintype "passive"))
      (node (ref "R37") (pin "1") (pinfunction "1_1") (pintype "passive"))
      (node (ref "R38") (pin "2") (pinfunction "2_2") (pintype "passive"))
      (node (ref "R41") (pin "2") (pinfunction "2_2") (pintype "passive"))
      (node (ref "U$17") (pin "3") (pinfunction "P3_3") (pintype "bidirectional"))
    )
    (net (code "49") (name "Net-(U1-GATE)") (class "Default")
      (node (ref "R16") (pin "P$2") (pinfunction "P$2_P$2") (pintype "passive"))
      (node (ref "U1") (pin "P$1") (pinfunction "GATE_P$1") (pintype "bidirectional"))
    )
    (net (code "50") (name "Net-(U2-EN)") (class "Default")
      (node (ref "C1") (pin "1") (pinfunction "1_1") (pintype "passive"))
      (node (ref "D2") (pin "1") (pinfunction "1_1") (pintype "bidirectional"))
      (node (ref "R35") (pin "P$2") (pinfunction "P$2_P$2") (pintype "passive"))
      (node (ref "U2") (pin "P$1") (pinfunction "VIN_P$1") (pintype "bidirectional"))
      (node (ref "U2") (pin "P$3") (pinfunction "EN_P$3") (pintype "bidirectional"))
    )
    (net (code "51") (name "SCK") (class "Default")
      (node (ref "JP5") (pin "3") (pinfunction "3_3") (pintype "passive"))
      (node (ref "U$1") (pin "P15") (pinfunction "PA5_P15") (pintype "bidirectional"))
    )
    (net (code "52") (name "SCL") (class "Default")
      (node (ref "JP6") (pin "4") (pinfunction "4_4") (pintype "passive"))
      (node (ref "U$1") (pin "P6") (pinfunction "PF1_P6") (pintype "bidirectional"))
    )
    (net (code "53") (name "SDA") (class "Default")
      (node (ref "JP6") (pin "2") (pinfunction "2_2") (pintype "passive"))
      (node (ref "U$1") (pin "P5") (pinfunction "PF0_P5") (pintype "bidirectional"))
    )
    (net (code "54") (name "SPI_CS") (class "Default")
      (node (ref "JP5") (pin "5") (pinfunction "5_5") (pintype "passive"))
      (node (ref "U$1") (pin "P18") (pinfunction "PB0_P18") (pintype "bidirectional"))
    )
    (net (code "55") (name "SWCLK") (class "Default")
      (node (ref "JP1") (pin "3") (pinfunction "3_3") (pintype "passive"))
      (node (ref "U$1") (pin "P37") (pinfunction "PA14_P37") (pintype "bidirectional"))
    )
    (net (code "56") (name "SWDIO") (class "Default")
      (node (ref "JP1") (pin "5") (pinfunction "5_5") (pintype "passive"))
      (node (ref "U$1") (pin "P34") (pinfunction "PA13_P34") (pintype "bidirectional"))
    )
    (net (code "57") (name "USB_DM") (class "Default")
      (node (ref "J1") (pin "2") (pinfunction "D-_2") (pintype "bidirectional"))
      (node (ref "U$1") (pin "P32") (pinfunction "PA11_P32") (pintype "bidirectional"))
      (node (ref "U$12") (pin "P1") (pinfunction "IO1_P1") (pintype "bidirectional"))
    )
    (net (code "58") (name "USB_DP") (class "Default")
      (node (ref "J1") (pin "3") (pinfunction "D+_3") (pintype "bidirectional"))
      (node (ref "U$1") (pin "P33") (pinfunction "PA12_P33") (pintype "bidirectional"))
      (node (ref "U$12") (pin "P3") (pinfunction "IO2_P3") (pintype "bidirectional"))
    )
    (net (code "59") (name "VUSB") (class "Default")
      (node (ref "C17") (pin "P$1") (pinfunction "P$1_P$1") (pintype "passive"))
      (node (ref "C18") (pin "P$1") (pinfunction "P$1_P$1") (pintype "passive"))
      (node (ref "C19") (pin "P$1") (pinfunction "P$1_P$1") (pintype "passive"))
      (node (ref "C20") (pin "P$1") (pinfunction "P$1_P$1") (pintype "passive"))
      (node (ref "C9") (pin "P$1") (pinfunction "P$1_P$1") (pintype "passive"))
      (node (ref "D2") (pin "2") (pinfunction "2_2") (pintype "bidirectional"))
      (node (ref "JP1") (pin "2") (pinfunction "2_2") (pintype "passive"))
      (node (ref "L1") (pin "1") (pinfunction "1_1") (pintype "passive"))
      (node (ref "R19") (pin "1") (pinfunction "1_1") (pintype "passive"))
      (node (ref "U$10") (pin "CATHODE") (pinfunction "CATHODE_CATHODE") (pintype "bidirectional"))
      (node (ref "U$12") (pin "P5") (pinfunction "VCC_P5") (pintype "power_in"))
      (node (ref "U$13") (pin "CATHODE") (pinfunction "CATHODE_CATHODE") (pintype "bidirectional"))
      (node (ref "U$14") (pin "P$1") (pinfunction "P$1_P$1") (pintype "bidirectional"))
      (node (ref "U$15") (pin "2") (pinfunction "P2_2") (pintype "power_in"))
      (node (ref "U$16") (pin "2") (pinfunction "P2_2") (pintype "power_in"))
      (node (ref "U$17") (pin "2") (pinfunction "P2_2") (pintype "power_in"))
      (node (ref "U$7") (pin "2") (pinfunction "P2_2") (pintype "power_in"))
      (node (ref "U$8") (pin "5") (pinfunction "VIN_5") (pintype "bidirectional"))
    )
    (net (code "60") (name "XCOARSE_IN") (class "Default")
      (node (ref "R5") (pin "1") (pinfunction "1_1") (pintype "passive"))
      (node (ref "U$1") (pin "P38") (pinfunction "PA15_P38") (pintype "bidirectional"))
      (node (ref "U$2") (pin "P1") (pinfunction "A1_P1") (pintype "input"))
    )
    (net (code "61") (name "XFINE_IN") (class "Default")
      (node (ref "R31") (pin "1") (pinfunction "1_1") (pintype "passive"))
      (node (ref "R6") (pin "1") (pinfunction "1_1") (pintype "passive"))
      (node (ref "U$1") (pin "P39") (pinfunction "PB3_P39") (pintype "bidirectional"))
      (node (ref "U$2") (pin "P3") (pinfunction "A2_P3") (pintype "input"))
    )
    (net (code "62") (name "YCOARSE_IN") (class "Default")
      (node (ref "R27") (pin "1") (pinfunction "1_1") (pintype "passive"))
      (node (ref "U$1") (pin "P21") (pinfunction "PB10_P21") (pintype "bidirectional"))
      (node (ref "U$4") (pin "P1") (pinfunction "A1_P1") (pintype "input"))
    )
    (net (code "63") (name "YFINE_IN") (class "Default")
      (node (ref "R30") (pin "1") (pinfunction "1_1") (pintype "passive"))
      (node (ref "R33") (pin "1") (pinfunction "1_1") (pintype "passive"))
      (node (ref "U$1") (pin "P22") (pinfunction "PB11_P22") (pintype "bidirectional"))
      (node (ref "U$4") (pin "P3") (pinfunction "A2_P3") (pintype "input"))
    )
    (net (code "64") (name "unconnected-(U$1-PA4-PadP14)") (class "Default")
      (node (ref "U$1") (pin "P14") (pinfunction "PA4_P14") (pintype "bidirectional"))
    )
    (net (code "65") (name "unconnected-(U$1-PA8-PadP29)") (class "Default")
      (node (ref "U$1") (pin "P29") (pinfunction "PA8_P29") (pintype "bidirectional"))
    )
    (net (code "66") (name "unconnected-(U$1-PA9-PadP30)") (class "Default")
      (node (ref "U$1") (pin "P30") (pinfunction "PA9_P30") (pintype "bidirectional"))
    )
    (net (code "67") (name "unconnected-(U$1-PA10-PadP31)") (class "Default")
      (node (ref "U$1") (pin "P31") (pinfunction "PA10_P31") (pintype "bidirectional"))
    )
    (net (code "68") (name "unconnected-(U$1-PB1-PadP19)") (class "Default")
      (node (ref "U$1") (pin "P19") (pinfunction "PB1_P19") (pintype "bidirectional"))
    )
    (net (code "69") (name "unconnected-(U$1-PB2-PadP20)") (class "Default")
      (node (ref "U$1") (pin "P20") (pinfunction "PB2_P20") (pintype "bidirectional"))
    )
    (net (code "70") (name "unconnected-(U$1-PB5-PadP41)") (class "Default")
      (node (ref "U$1") (pin "P41") (pinfunction "PB5_P41") (pintype "bidirectional"))
    )
    (net (code "71") (name "unconnected-(U$1-PB6-PadP42)") (class "Default")
      (node (ref "U$1") (pin "P42") (pinfunction "PB6_P42") (pintype "bidirectional"))
    )
    (net (code "72") (name "unconnected-(U$1-PB7-PadP43)") (class "Default")
      (node (ref "U$1") (pin "P43") (pinfunction "PB7_P43") (pintype "bidirectional"))
    )
    (net (code "73") (name "unconnected-(U$1-PB8-PadP45)") (class "Default")
      (node (ref "U$1") (pin "P45") (pinfunction "PB8_P45") (pintype "bidirectional"))
    )
    (net (code "74") (name "unconnected-(U$1-PB9-PadP46)") (class "Default")
      (node (ref "U$1") (pin "P46") (pinfunction "PB9_P46") (pintype "bidirectional"))
    )
    (net (code "75") (name "unconnected-(U$1-PC13-PadP2)") (class "Default")
      (node (ref "U$1") (pin "P2") (pinfunction "PC13_P2") (pintype "bidirectional"))
    )
    (net (code "76") (name "unconnected-(U$1-PC14-PadP3)") (class "Default")
      (node (ref "U$1") (pin "P3") (pinfunction "PC14_P3") (pintype "bidirectional"))
    )
    (net (code "77") (name "unconnected-(U$1-PC15-PadP4)") (class "Default")
      (node (ref "U$1") (pin "P4") (pinfunction "PC15_P4") (pintype "bidirectional"))
    )
    (net (code "78") (name "unconnected-(U$12-IO3-PadP4)") (class "Default")
      (node (ref "U$12") (pin "P4") (pinfunction "IO3_P4") (pintype "bidirectional"))
    )
    (net (code "79") (name "unconnected-(U$12-IO4-PadP6)") (class "Default")
      (node (ref "U$12") (pin "P6") (pinfunction "IO4_P6") (pintype "bidirectional"))
    )
  )
)
